# RAY_SolarModule2.net
KiCad netlist of a schematic drawn in EAGLE
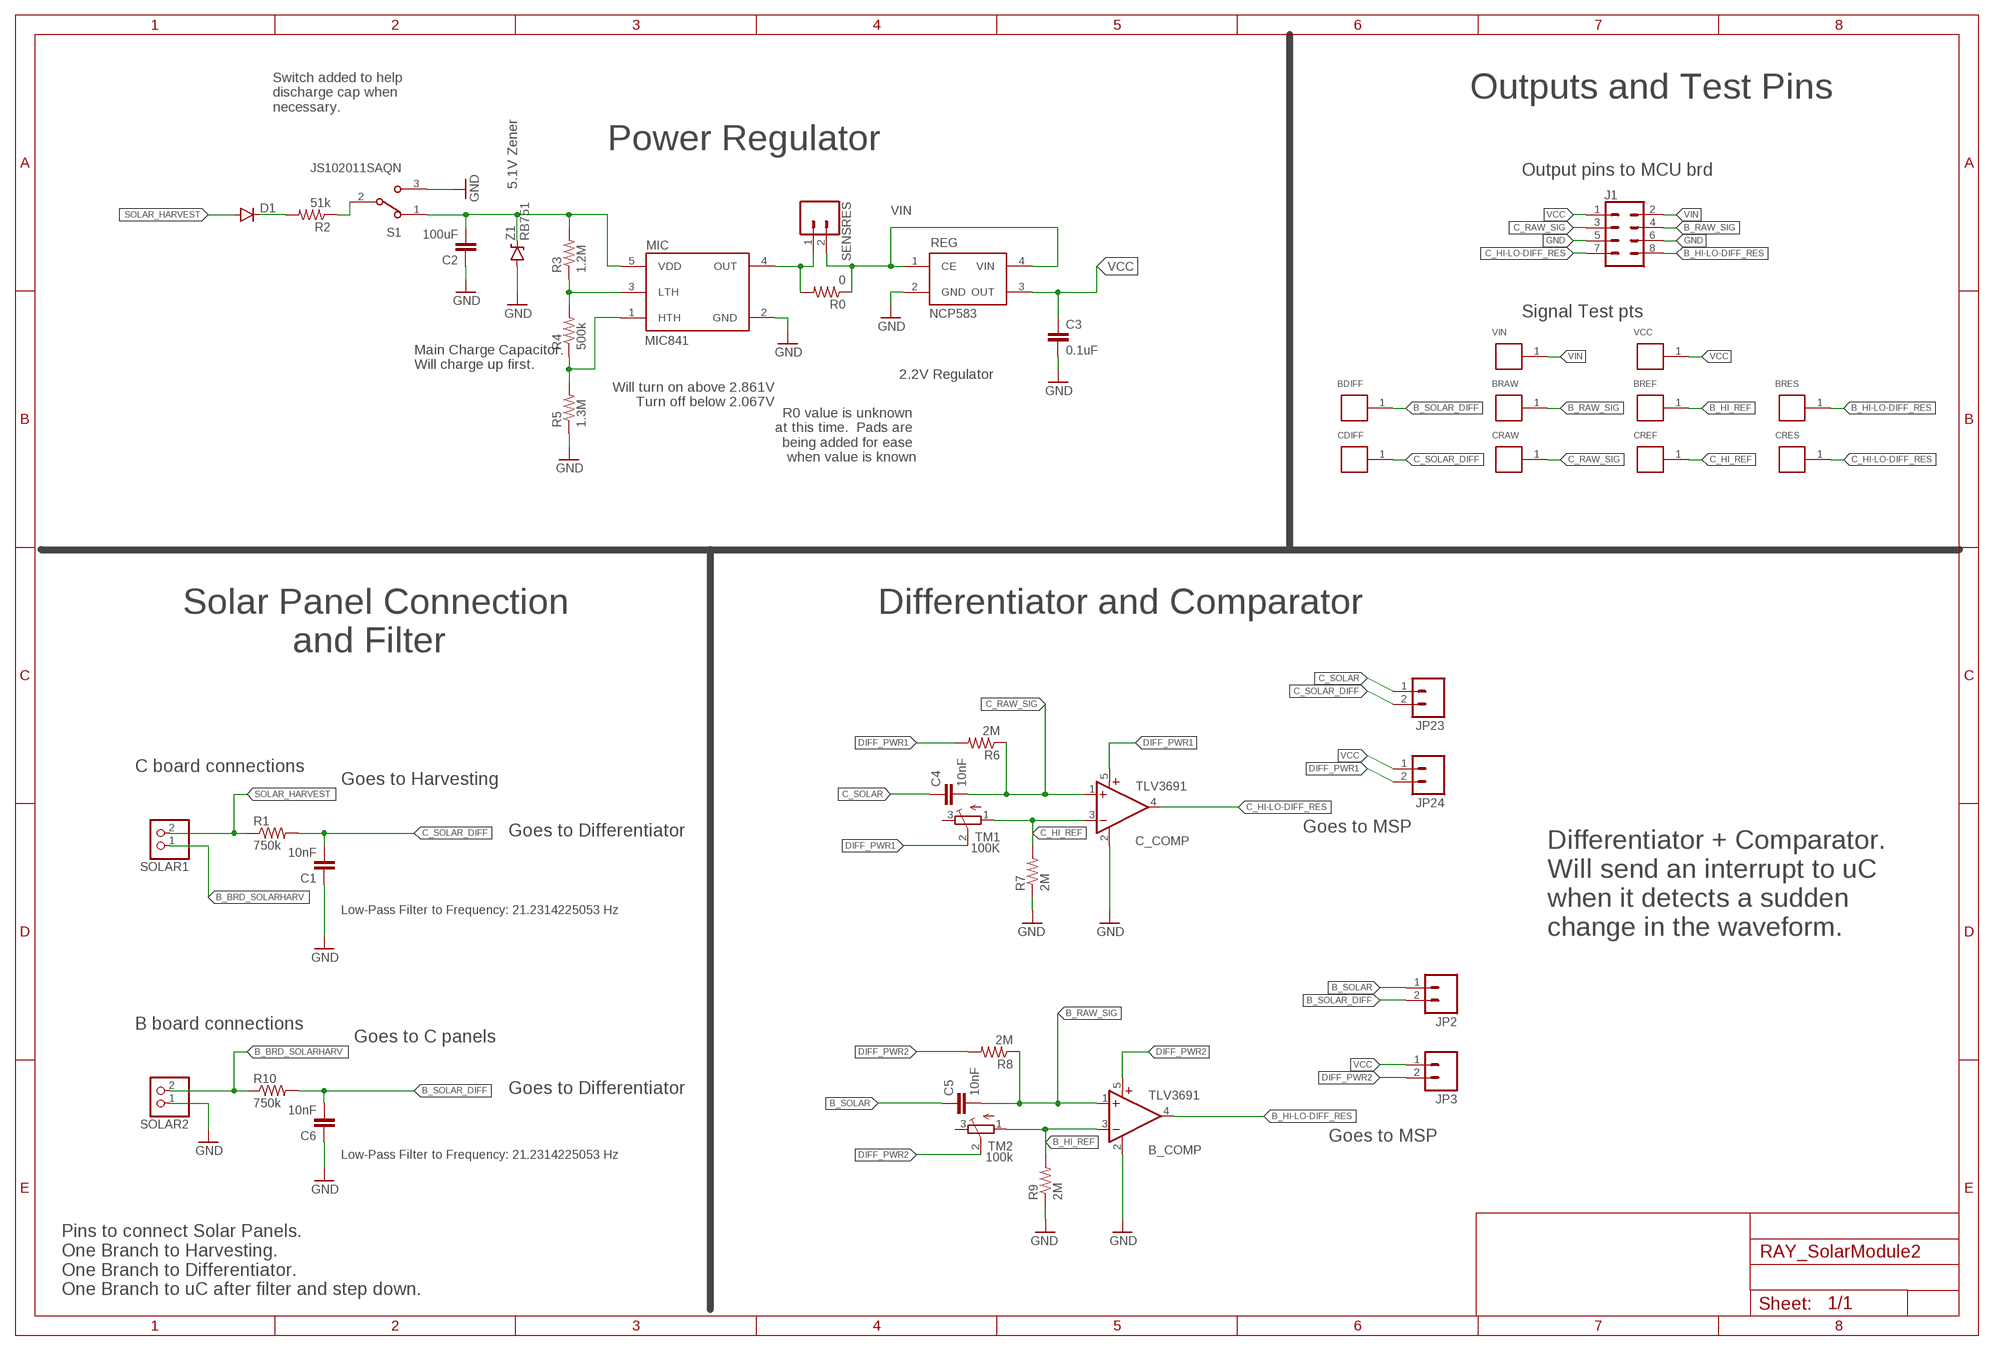
[diagram p0: schematic, sheet 1]

(export (version "E")
  (design (tool "Eeschema 10.0.6"))
  (components
    (comp (ref "BDIFF")
      (value "RCU-0C")
      (footprint "eagle-import:TE_RCU-0C")
      (fields
        (field (name "COMMENT") "RCU-0C _1625854-3_")
        (field (name "MF") "TE Connectivity")
        (field (name "TOLERANCE") "0%")
      )
      (libsource (lib "eagle-import") (part "RCU-0C"))
    )
    (comp (ref "BRAW")
      (value "RCU-0C")
      (footprint "eagle-import:TE_RCU-0C")
      (fields
        (field (name "COMMENT") "RCU-0C _1625854-3_")
        (field (name "MF") "TE Connectivity")
        (field (name "TOLERANCE") "0%")
      )
      (libsource (lib "eagle-import") (part "RCU-0C"))
    )
    (comp (ref "BREF")
      (value "RCU-0C")
      (footprint "eagle-import:TE_RCU-0C")
      (fields
        (field (name "COMMENT") "RCU-0C _1625854-3_")
        (field (name "MF") "TE Connectivity")
        (field (name "TOLERANCE") "0%")
      )
      (libsource (lib "eagle-import") (part "RCU-0C"))
    )
    (comp (ref "BRES")
      (value "RCU-0C")
      (footprint "eagle-import:TE_RCU-0C")
      (fields
        (field (name "COMMENT") "RCU-0C _1625854-3_")
        (field (name "MF") "TE Connectivity")
        (field (name "TOLERANCE") "0%")
      )
      (libsource (lib "eagle-import") (part "RCU-0C"))
    )
    (comp (ref "B_COMP")
      (value "TLV3691")
      (footprint "eagle-import:SC70-5")
      (libsource (lib "eagle-import") (part "TLV3691"))
    )
    (comp (ref "C1")
      (value "10nF")
      (footprint "eagle-import:0603-CAP")
      (libsource (lib "eagle-import") (part "CAP0603-CAP"))
    )
    (comp (ref "C2")
      (value "100uF")
      (footprint "eagle-import:0603-CAP")
      (libsource (lib "eagle-import") (part "CAP0603-CAP"))
    )
    (comp (ref "C3")
      (value "0.1uF")
      (footprint "eagle-import:0603-CAP")
      (libsource (lib "eagle-import") (part "CAP0603-CAP"))
    )
    (comp (ref "C4")
      (value "10nF")
      (footprint "eagle-import:0603-CAP")
      (libsource (lib "eagle-import") (part "CAP0603-CAP"))
    )
    (comp (ref "C5")
      (value "10nF")
      (footprint "eagle-import:0603-CAP")
      (libsource (lib "eagle-import") (part "CAP0603-CAP"))
    )
    (comp (ref "C6")
      (value "10nF")
      (footprint "eagle-import:0603-CAP")
      (libsource (lib "eagle-import") (part "CAP0603-CAP"))
    )
    (comp (ref "CDIFF")
      (value "RCU-0C")
      (footprint "eagle-import:TE_RCU-0C")
      (fields
        (field (name "COMMENT") "RCU-0C _1625854-3_")
        (field (name "MF") "TE Connectivity")
        (field (name "TOLERANCE") "0%")
      )
      (libsource (lib "eagle-import") (part "RCU-0C"))
    )
    (comp (ref "CRAW")
      (value "RCU-0C")
      (footprint "eagle-import:TE_RCU-0C")
      (fields
        (field (name "COMMENT") "RCU-0C _1625854-3_")
        (field (name "MF") "TE Connectivity")
        (field (name "TOLERANCE") "0%")
      )
      (libsource (lib "eagle-import") (part "RCU-0C"))
    )
    (comp (ref "CREF")
      (value "RCU-0C")
      (footprint "eagle-import:TE_RCU-0C")
      (fields
        (field (name "COMMENT") "RCU-0C _1625854-3_")
        (field (name "MF") "TE Connectivity")
        (field (name "TOLERANCE") "0%")
      )
      (libsource (lib "eagle-import") (part "RCU-0C"))
    )
    (comp (ref "CRES")
      (value "RCU-0C")
      (footprint "eagle-import:TE_RCU-0C")
      (fields
        (field (name "COMMENT") "RCU-0C _1625854-3_")
        (field (name "MF") "TE Connectivity")
        (field (name "TOLERANCE") "0%")
      )
      (libsource (lib "eagle-import") (part "RCU-0C"))
    )
    (comp (ref "C_COMP")
      (value "TLV3691")
      (footprint "eagle-import:SC70-5")
      (libsource (lib "eagle-import") (part "TLV3691"))
    )
    (comp (ref "D1")
      (value "DIODESOD523")
      (footprint "eagle-import:SOD523")
      (libsource (lib "eagle-import") (part "DIODESOD523"))
    )
    (comp (ref "J1")
      (value "CONN_04X2")
      (footprint "eagle-import:2X4")
      (libsource (lib "eagle-import") (part "CONN_04X2"))
    )
    (comp (ref "JP2")
      (value "M02")
      (footprint "eagle-import:1X02-1.27MM")
      (libsource (lib "eagle-import") (part "M02"))
    )
    (comp (ref "JP3")
      (value "M02")
      (footprint "eagle-import:1X02-1.27MM")
      (libsource (lib "eagle-import") (part "M02"))
    )
    (comp (ref "JP23")
      (value "M02")
      (footprint "eagle-import:1X02-1.27MM")
      (libsource (lib "eagle-import") (part "M02"))
    )
    (comp (ref "JP24")
      (value "M02")
      (footprint "eagle-import:1X02-1.27MM")
      (libsource (lib "eagle-import") (part "M02"))
    )
    (comp (ref "MIC")
      (value "MIC841")
      (footprint "eagle-import:SC70-5")
      (libsource (lib "eagle-import") (part "MIC841"))
    )
    (comp (ref "R0")
      (value "0")
      (footprint "eagle-import:0603-RES")
      (libsource (lib "eagle-import") (part "RESISTOR0603"))
    )
    (comp (ref "R1")
      (value "750k")
      (footprint "eagle-import:0603-RES")
      (libsource (lib "eagle-import") (part "RESISTOR0603"))
    )
    (comp (ref "R2")
      (value "51k")
      (footprint "eagle-import:0603-RES")
      (libsource (lib "eagle-import") (part "RESISTOR0603"))
    )
    (comp (ref "R3")
      (value "1.2M")
      (footprint "eagle-import:0603-RES")
      (libsource (lib "eagle-import") (part "RESISTOR0603"))
    )
    (comp (ref "R4")
      (value "500k")
      (footprint "eagle-import:0603-RES")
      (libsource (lib "eagle-import") (part "RESISTOR0603"))
    )
    (comp (ref "R5")
      (value "1.3M")
      (footprint "eagle-import:0603-RES")
      (libsource (lib "eagle-import") (part "RESISTOR0603"))
    )
    (comp (ref "R6")
      (value "2M")
      (footprint "eagle-import:0603-RES")
      (libsource (lib "eagle-import") (part "RESISTOR0603"))
    )
    (comp (ref "R7")
      (value "2M")
      (footprint "eagle-import:0603-RES")
      (libsource (lib "eagle-import") (part "RESISTOR0603"))
    )
    (comp (ref "R8")
      (value "2M")
      (footprint "eagle-import:0603-RES")
      (libsource (lib "eagle-import") (part "RESISTOR0603"))
    )
    (comp (ref "R9")
      (value "2M")
      (footprint "eagle-import:0603-RES")
      (libsource (lib "eagle-import") (part "RESISTOR0603"))
    )
    (comp (ref "R10")
      (value "750k")
      (footprint "eagle-import:0603-RES")
      (libsource (lib "eagle-import") (part "RESISTOR0603"))
    )
    (comp (ref "REG")
      (value "NCP583")
      (footprint "eagle-import:SC82-AB_1PRIMARY")
      (libsource (lib "eagle-import") (part "NCP583"))
    )
    (comp (ref "S1")
      (value "JS102011SAQN")
      (footprint "eagle-import:SW_JS102011SAQN")
      (fields (field (name "MF") "C&K Components"))
      (libsource (lib "eagle-import") (part "JS102011SAQN"))
    )
    (comp (ref "SENSRES")
      (value "CONN_02")
      (footprint "eagle-import:1X02")
      (libsource (lib "eagle-import") (part "CONN_02"))
    )
    (comp (ref "SOLAR1")
      (value "PINHD-1X2")
      (footprint "eagle-import:1X02")
      (libsource (lib "eagle-import") (part "PINHD-1X2"))
    )
    (comp (ref "SOLAR2")
      (value "PINHD-1X2")
      (footprint "eagle-import:1X02")
      (libsource (lib "eagle-import") (part "PINHD-1X2"))
    )
    (comp (ref "TM1")
      (value "100K")
      (footprint "eagle-import:TC33X")
      (libsource (lib "eagle-import") (part "TRIMPOTTC33X"))
    )
    (comp (ref "TM2")
      (value "100k")
      (footprint "eagle-import:TC33X")
      (libsource (lib "eagle-import") (part "TRIMPOTTC33X"))
    )
    (comp (ref "VCC")
      (value "RCU-0C")
      (footprint "eagle-import:TE_RCU-0C")
      (fields
        (field (name "COMMENT") "RCU-0C _1625854-3_")
        (field (name "MF") "TE Connectivity")
        (field (name "TOLERANCE") "0%")
      )
      (libsource (lib "eagle-import") (part "RCU-0C"))
    )
    (comp (ref "VIN")
      (value "RCU-0C")
      (footprint "eagle-import:TE_RCU-0C")
      (fields
        (field (name "COMMENT") "RCU-0C _1625854-3_")
        (field (name "MF") "TE Connectivity")
        (field (name "TOLERANCE") "0%")
      )
      (libsource (lib "eagle-import") (part "RCU-0C"))
    )
    (comp (ref "Z1")
      (value "RB751")
      (footprint "eagle-import:SOD-523")
      (libsource (lib "eagle-import") (part "DIODE-ZENER"))
    )
  )
  (nets
    (net (code "1") (name "B_BRD_SOLARHARV") (class "Default")
      (node (ref "R10") (pin "1") (pinfunction "1_1") (pintype "passive"))
      (node (ref "SOLAR1") (pin "1") (pinfunction "1_1") (pintype "passive"))
      (node (ref "SOLAR2") (pin "2") (pinfunction "2_2") (pintype "passive"))
    )
    (net (code "2") (name "B_HI-LO-DIFF_RES") (class "Default")
      (node (ref "BRES") (pin "1") (pinfunction "1_1") (pintype "passive"))
      (node (ref "B_COMP") (pin "4") (pinfunction "OUT_4") (pintype "output"))
      (node (ref "J1") (pin "8") (pinfunction "8_8") (pintype "passive"))
    )
    (net (code "3") (name "B_HI_REF") (class "Default")
      (node (ref "BREF") (pin "1") (pinfunction "1_1") (pintype "passive"))
      (node (ref "B_COMP") (pin "3") (pinfunction "-IN_3") (pintype "input"))
      (node (ref "R9") (pin "2") (pinfunction "2_2") (pintype "passive"))
      (node (ref "TM2") (pin "1") (pinfunction "A_1") (pintype "passive"))
    )
    (net (code "4") (name "B_RAW_SIG") (class "Default")
      (node (ref "BRAW") (pin "1") (pinfunction "1_1") (pintype "passive"))
      (node (ref "B_COMP") (pin "1") (pinfunction "+IN_1") (pintype "input"))
      (node (ref "C5") (pin "2") (pinfunction "2_2") (pintype "passive"))
      (node (ref "J1") (pin "4") (pinfunction "4_4") (pintype "passive"))
      (node (ref "R8") (pin "1") (pinfunction "1_1") (pintype "passive"))
    )
    (net (code "5") (name "B_SOLAR") (class "Default")
      (node (ref "C5") (pin "1") (pinfunction "1_1") (pintype "passive"))
      (node (ref "JP2") (pin "1") (pinfunction "1_1") (pintype "passive"))
    )
    (net (code "6") (name "B_SOLAR_DIFF") (class "Default")
      (node (ref "BDIFF") (pin "1") (pinfunction "1_1") (pintype "passive"))
      (node (ref "C6") (pin "2") (pinfunction "2_2") (pintype "passive"))
      (node (ref "JP2") (pin "2") (pinfunction "2_2") (pintype "passive"))
      (node (ref "R10") (pin "2") (pinfunction "2_2") (pintype "passive"))
    )
    (net (code "7") (name "C_HI-LO-DIFF_RES") (class "Default")
      (node (ref "CRES") (pin "1") (pinfunction "1_1") (pintype "passive"))
      (node (ref "C_COMP") (pin "4") (pinfunction "OUT_4") (pintype "output"))
      (node (ref "J1") (pin "7") (pinfunction "7_7") (pintype "passive"))
    )
    (net (code "8") (name "C_HI_REF") (class "Default")
      (node (ref "CREF") (pin "1") (pinfunction "1_1") (pintype "passive"))
      (node (ref "C_COMP") (pin "3") (pinfunction "-IN_3") (pintype "input"))
      (node (ref "R7") (pin "2") (pinfunction "2_2") (pintype "passive"))
      (node (ref "TM1") (pin "1") (pinfunction "A_1") (pintype "passive"))
    )
    (net (code "9") (name "C_RAW_SIG") (class "Default")
      (node (ref "C4") (pin "2") (pinfunction "2_2") (pintype "passive"))
      (node (ref "CRAW") (pin "1") (pinfunction "1_1") (pintype "passive"))
      (node (ref "C_COMP") (pin "1") (pinfunction "+IN_1") (pintype "input"))
      (node (ref "J1") (pin "3") (pinfunction "3_3") (pintype "passive"))
      (node (ref "R6") (pin "1") (pinfunction "1_1") (pintype "passive"))
    )
    (net (code "10") (name "C_SOLAR") (class "Default")
      (node (ref "C4") (pin "1") (pinfunction "1_1") (pintype "passive"))
      (node (ref "JP23") (pin "1") (pinfunction "1_1") (pintype "passive"))
    )
    (net (code "11") (name "C_SOLAR_DIFF") (class "Default")
      (node (ref "C1") (pin "2") (pinfunction "2_2") (pintype "passive"))
      (node (ref "CDIFF") (pin "1") (pinfunction "1_1") (pintype "passive"))
      (node (ref "JP23") (pin "2") (pinfunction "2_2") (pintype "passive"))
      (node (ref "R1") (pin "2") (pinfunction "2_2") (pintype "passive"))
    )
    (net (code "12") (name "DIFF_PWR1") (class "Default")
      (node (ref "C_COMP") (pin "5") (pinfunction "V+_5") (pintype "power_in"))
      (node (ref "JP24") (pin "2") (pinfunction "2_2") (pintype "passive"))
      (node (ref "R6") (pin "2") (pinfunction "2_2") (pintype "passive"))
      (node (ref "TM1") (pin "2") (pinfunction "S_2") (pintype "passive"))
    )
    (net (code "13") (name "DIFF_PWR2") (class "Default")
      (node (ref "B_COMP") (pin "5") (pinfunction "V+_5") (pintype "power_in"))
      (node (ref "JP3") (pin "2") (pinfunction "2_2") (pintype "passive"))
      (node (ref "R8") (pin "2") (pinfunction "2_2") (pintype "passive"))
      (node (ref "TM2") (pin "2") (pinfunction "S_2") (pintype "passive"))
    )
    (net (code "14") (name "GND") (class "Default")
      (node (ref "B_COMP") (pin "2") (pinfunction "GND_2") (pintype "power_in"))
      (node (ref "C1") (pin "1") (pinfunction "1_1") (pintype "passive"))
      (node (ref "C2") (pin "1") (pinfunction "1_1") (pintype "passive"))
      (node (ref "C3") (pin "2") (pinfunction "2_2") (pintype "passive"))
      (node (ref "C6") (pin "1") (pinfunction "1_1") (pintype "passive"))
      (node (ref "C_COMP") (pin "2") (pinfunction "GND_2") (pintype "power_in"))
      (node (ref "J1") (pin "5") (pinfunction "5_5") (pintype "passive"))
      (node (ref "J1") (pin "6") (pinfunction "6_6") (pintype "passive"))
      (node (ref "MIC") (pin "2") (pinfunction "GND_2") (pintype "bidirectional"))
      (node (ref "R5") (pin "1") (pinfunction "1_1") (pintype "passive"))
      (node (ref "R7") (pin "1") (pinfunction "1_1") (pintype "passive"))
      (node (ref "R9") (pin "1") (pinfunction "1_1") (pintype "passive"))
      (node (ref "REG") (pin "2") (pinfunction "GND_2") (pintype "bidirectional"))
      (node (ref "S1") (pin "3") (pinfunction "3_3") (pintype "passive"))
      (node (ref "SOLAR2") (pin "1") (pinfunction "1_1") (pintype "passive"))
      (node (ref "Z1") (pin "ANODE") (pinfunction "A_ANODE") (pintype "passive"))
    )
    (net (code "15") (name "Net-(D1-PadC)") (class "Default")
      (node (ref "D1") (pin "C") (pinfunction "C_C") (pintype "passive"))
      (node (ref "R2") (pin "2") (pinfunction "2_2") (pintype "passive"))
    )
    (net (code "16") (name "Net-(MIC-HTH)") (class "Default")
      (node (ref "MIC") (pin "1") (pinfunction "HTH_1") (pintype "bidirectional"))
      (node (ref "R4") (pin "1") (pinfunction "1_1") (pintype "passive"))
      (node (ref "R5") (pin "2") (pinfunction "2_2") (pintype "passive"))
    )
    (net (code "17") (name "Net-(MIC-LTH)") (class "Default")
      (node (ref "MIC") (pin "3") (pinfunction "LTH_3") (pintype "bidirectional"))
      (node (ref "R3") (pin "1") (pinfunction "1_1") (pintype "passive"))
      (node (ref "R4") (pin "2") (pinfunction "2_2") (pintype "passive"))
    )
    (net (code "18") (name "Net-(MIC-OUT)") (class "Default")
      (node (ref "MIC") (pin "4") (pinfunction "OUT_4") (pintype "bidirectional"))
      (node (ref "R0") (pin "2") (pinfunction "2_2") (pintype "passive"))
      (node (ref "SENSRES") (pin "1") (pinfunction "1_1") (pintype "passive"))
    )
    (net (code "19") (name "Net-(MIC-VDD)") (class "Default")
      (node (ref "C2") (pin "2") (pinfunction "2_2") (pintype "passive"))
      (node (ref "MIC") (pin "5") (pinfunction "VDD_5") (pintype "bidirectional"))
      (node (ref "R3") (pin "2") (pinfunction "2_2") (pintype "passive"))
      (node (ref "S1") (pin "1") (pinfunction "1_1") (pintype "passive"))
      (node (ref "Z1") (pin "CATHODE") (pinfunction "C_CATHODE") (pintype "passive"))
    )
    (net (code "20") (name "Net-(R2-Pad1)") (class "Default")
      (node (ref "R2") (pin "1") (pinfunction "1_1") (pintype "passive"))
      (node (ref "S1") (pin "2") (pinfunction "2_2") (pintype "passive"))
    )
    (net (code "21") (name "SOLAR_HARVEST") (class "Default")
      (node (ref "D1") (pin "A") (pinfunction "A_A") (pintype "passive"))
      (node (ref "R1") (pin "1") (pinfunction "1_1") (pintype "passive"))
      (node (ref "SOLAR1") (pin "2") (pinfunction "2_2") (pintype "passive"))
    )
    (net (code "22") (name "VCC") (class "Default")
      (node (ref "C3") (pin "1") (pinfunction "1_1") (pintype "passive"))
      (node (ref "J1") (pin "1") (pinfunction "1_1") (pintype "passive"))
      (node (ref "JP24") (pin "1") (pinfunction "1_1") (pintype "passive"))
      (node (ref "JP3") (pin "1") (pinfunction "1_1") (pintype "passive"))
      (node (ref "REG") (pin "3") (pinfunction "OUT_3") (pintype "bidirectional"))
      (node (ref "VCC") (pin "1") (pinfunction "1_1") (pintype "passive"))
    )
    (net (code "23") (name "VIN") (class "Default")
      (node (ref "J1") (pin "2") (pinfunction "2_2") (pintype "passive"))
      (node (ref "R0") (pin "1") (pinfunction "1_1") (pintype "passive"))
      (node (ref "REG") (pin "1") (pinfunction "CE_1") (pintype "bidirectional"))
      (node (ref "REG") (pin "4") (pinfunction "VIN_4") (pintype "bidirectional"))
      (node (ref "SENSRES") (pin "2") (pinfunction "2_2") (pintype "passive"))
      (node (ref "VIN") (pin "1") (pinfunction "1_1") (pintype "passive"))
    )
    (net (code "24") (name "unconnected-(TM1-E-Pad3)") (class "Default")
      (node (ref "TM1") (pin "3") (pinfunction "E_3") (pintype "passive"))
    )
    (net (code "25") (name "unconnected-(TM2-E-Pad3)") (class "Default")
      (node (ref "TM2") (pin "3") (pinfunction "E_3") (pintype "passive"))
    )
  )
)
